# Rangkaian_GT.net
KiCad netlist of a schematic drawn in EAGLE
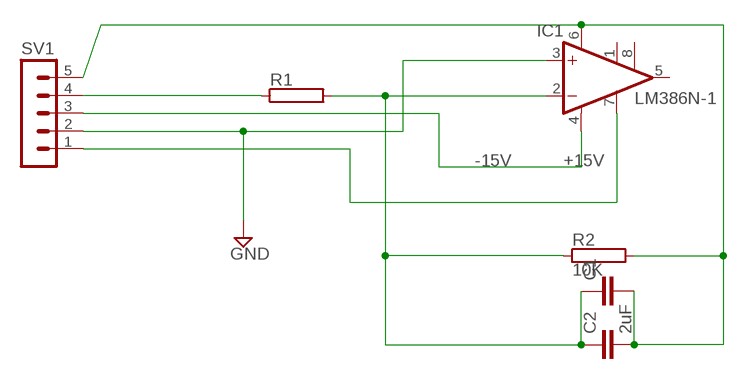
[diagram p0: schematic, sheet 1]

(export (version "E")
  (design (tool "Eeschema 10.0.6"))
  (components
    (comp (ref "C1")
      (value "C-EU025-024X044")
      (footprint "eagle-import:C025-024X044")
      (libsource (lib "eagle-import") (part "C-EU025-024X044"))
    )
    (comp (ref "C2")
      (value "2uF")
      (footprint "eagle-import:C025-024X044")
      (libsource (lib "eagle-import") (part "C-EU025-024X044"))
    )
    (comp (ref "IC1")
      (value "LM386N-1")
      (footprint "eagle-import:DIL08")
      (libsource (lib "eagle-import") (part "LM386?-N1"))
    )
    (comp (ref "R1")
      (value "RCA5050")
      (footprint "eagle-import:CA5050")
      (libsource (lib "eagle-import") (part "RCA5050"))
    )
    (comp (ref "R2")
      (value "10K")
      (footprint "eagle-import:CA5050")
      (libsource (lib "eagle-import") (part "RCA5050"))
    )
    (comp (ref "SV1")
      (value "MA05-1")
      (footprint "eagle-import:MA05-1")
      (libsource (lib "eagle-import") (part "MA05-1"))
    )
  )
  (nets
    (net (code "1") (name "/+15V") (class "Default")
      (node (ref "IC1") (pin "7") (pinfunction "BYPASS_7") (pintype "passive"))
      (node (ref "SV1") (pin "1") (pinfunction "1_1") (pintype "passive"))
    )
    (net (code "2") (name "/-15V") (class "Default")
      (node (ref "IC1") (pin "4") (pinfunction "GND_4") (pintype "power_in"))
      (node (ref "SV1") (pin "3") (pinfunction "3_3") (pintype "passive"))
    )
    (net (code "3") (name "GND") (class "Default")
      (node (ref "IC1") (pin "3") (pinfunction "+IN_3") (pintype "input"))
      (node (ref "SV1") (pin "2") (pinfunction "2_2") (pintype "passive"))
    )
    (net (code "4") (name "Net-(IC1--IN)") (class "Default")
      (node (ref "C1") (pin "1") (pinfunction "1_1") (pintype "passive"))
      (node (ref "C2") (pin "1") (pinfunction "1_1") (pintype "passive"))
      (node (ref "IC1") (pin "2") (pinfunction "-IN_2") (pintype "input"))
      (node (ref "R1") (pin "2") (pinfunction "2_2") (pintype "passive"))
      (node (ref "R2") (pin "1") (pinfunction "1_1") (pintype "passive"))
    )
    (net (code "5") (name "Net-(IC1-VS)") (class "Default")
      (node (ref "C1") (pin "2") (pinfunction "2_2") (pintype "passive"))
      (node (ref "C2") (pin "2") (pinfunction "2_2") (pintype "passive"))
      (node (ref "IC1") (pin "6") (pinfunction "VS_6") (pintype "power_in"))
      (node (ref "R2") (pin "2") (pinfunction "2_2") (pintype "passive"))
      (node (ref "SV1") (pin "5") (pinfunction "5_5") (pintype "passive"))
    )
    (net (code "6") (name "Net-(R1-Pad1)") (class "Default")
      (node (ref "R1") (pin "1") (pinfunction "1_1") (pintype "passive"))
      (node (ref "SV1") (pin "4") (pinfunction "4_4") (pintype "passive"))
    )
    (net (code "7") (name "unconnected-(IC1-GAIN-Pad1)") (class "Default")
      (node (ref "IC1") (pin "1") (pinfunction "GAIN_1") (pintype "passive"))
    )
    (net (code "8") (name "unconnected-(IC1-GAIN-Pad8)") (class "Default")
      (node (ref "IC1") (pin "8") (pinfunction "GAIN_8") (pintype "passive"))
    )
    (net (code "9") (name "unconnected-(IC1-OUT-Pad5)") (class "Default")
      (node (ref "IC1") (pin "5") (pinfunction "OUT_5") (pintype "output"))
    )
  )
)
